# Arduino.net
KiCad netlist of a schematic drawn in Altium Designer
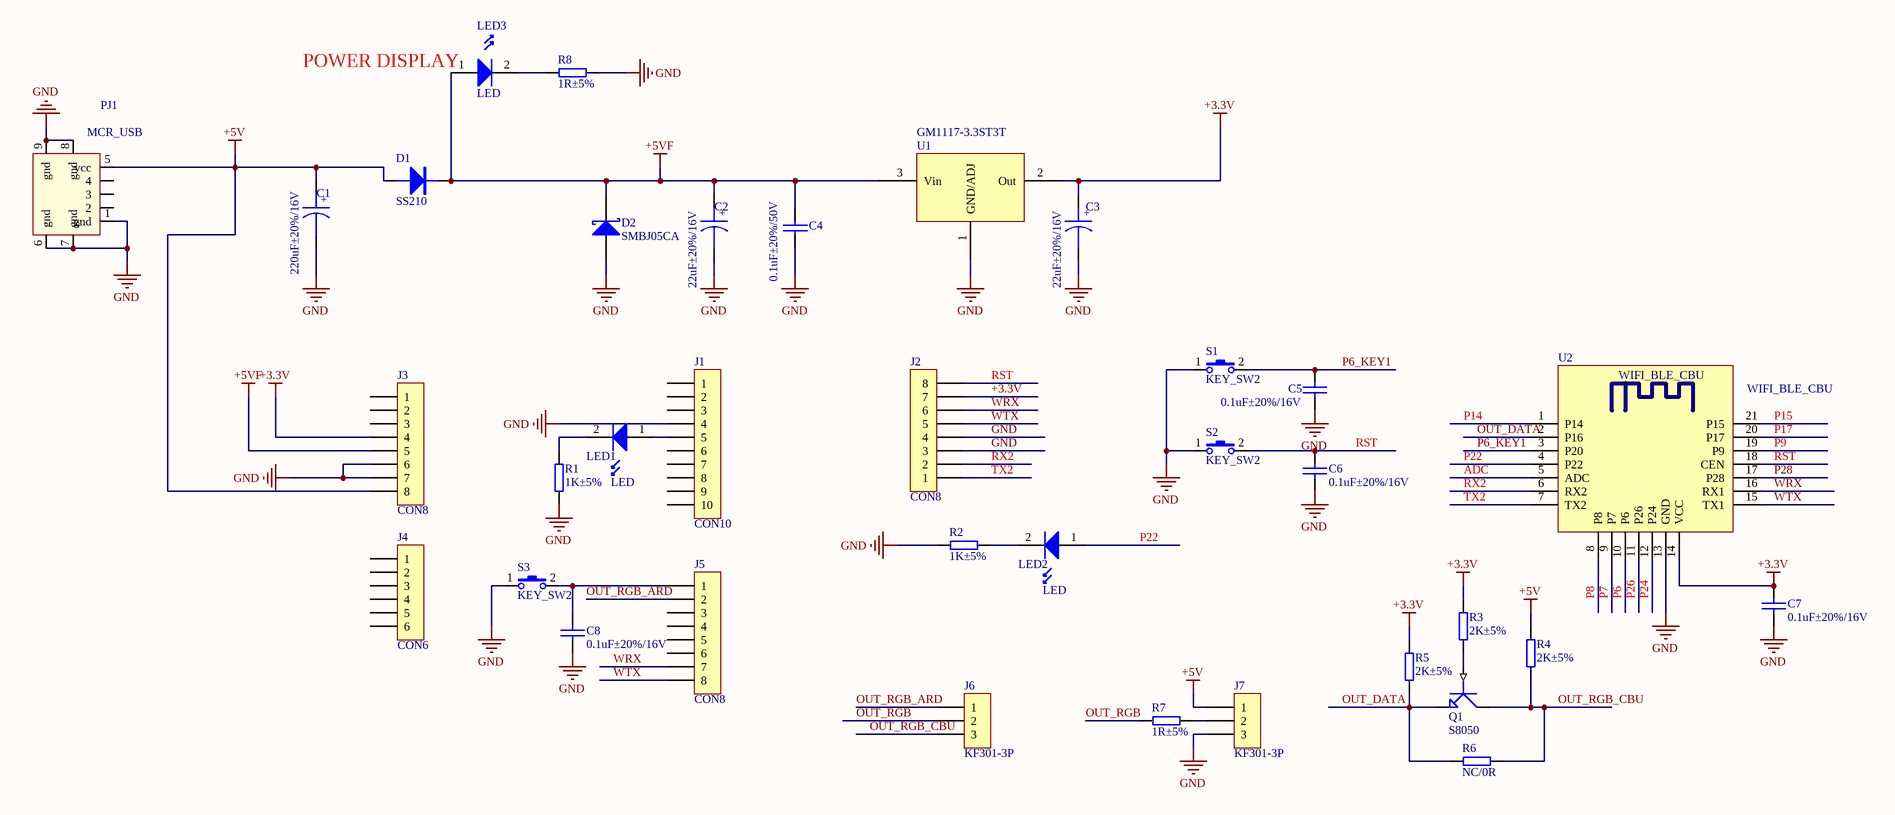
[diagram p0: Arduino幻彩灯带.SchDoc]

(export (version "E")
  (design (tool "Eeschema 10.0.6"))
  (components
    (comp (ref "C1")
      (value "220uF±20%/16V")
      (footprint "CD0.15")
      (description "Capacitor")
      (libsource (lib "*") (part "CAPACITOR POL"))
    )
    (comp (ref "C2")
      (value "22uF±20%/16V")
      (footprint "钽电容B3528")
      (description "Capacitor")
      (libsource (lib "*") (part "CAPACITOR POL"))
    )
    (comp (ref "C3")
      (value "22uF±20%/16V")
      (footprint "钽电容B3528")
      (description "Capacitor")
      (libsource (lib "*") (part "CAPACITOR POL"))
    )
    (comp (ref "C4")
      (value "0.1uF±20%/50V")
      (footprint "C0603")
      (description "Capacitor")
      (libsource (lib "昊华元件库sch") (part "CAP"))
    )
    (comp (ref "C5")
      (value "0.1uF±20%/16V")
      (footprint "C0603")
      (description "Capacitor")
      (libsource (lib "昊华元件库sch") (part "CAP"))
    )
    (comp (ref "C6")
      (value "0.1uF±20%/16V")
      (footprint "C0603")
      (description "Capacitor")
      (libsource (lib "昊华元件库sch") (part "CAP"))
    )
    (comp (ref "C7")
      (value "0.1uF±20%/16V")
      (footprint "C0603")
      (description "Capacitor")
      (libsource (lib "昊华元件库sch") (part "CAP"))
    )
    (comp (ref "C8")
      (value "0.1uF±20%/16V")
      (footprint "C0603")
      (description "Capacitor")
      (libsource (lib "昊华元件库sch") (part "CAP"))
    )
    (comp (ref "D1")
      (value "SS210")
      (footprint "SMA(DO-214AC)")
      (description "Diode")
      (libsource (lib "小马元件库sch") (part "Diode1"))
    )
    (comp (ref "D2")
      (value "SMBJ05CA")
      (footprint "SMB(DO-214AA)")
      (description "Schottky Diode")
      (fields (field (name "MFR") "Toshiba"))
      (libsource (lib "Miscellaneous Devices") (part "D Schottky"))
    )
    (comp (ref "J1")
      (value "CON10")
      (footprint "HDR1X10Z")
      (description "Connector")
      (libsource (lib "小马元件库sch") (part "CON10"))
    )
    (comp (ref "J2")
      (value "CON8")
      (footprint "HDR1X8Z")
      (description "Connector")
      (libsource (lib "") (part "CON8_1"))
    )
    (comp (ref "J3")
      (value "CON8")
      (footprint "HDR1X8Z")
      (description "Connector")
      (libsource (lib "小马元件库sch") (part "CON8"))
    )
    (comp (ref "J4")
      (value "CON6")
      (footprint "HDR1X6Z")
      (description "Connector")
      (libsource (lib "小马元件库sch") (part "CON6"))
    )
    (comp (ref "J5")
      (value "CON8")
      (footprint "HDR1X8Z")
      (description "Connector")
      (libsource (lib "小马元件库sch") (part "CON8"))
    )
    (comp (ref "J6")
      (value "KF301-3P")
      (footprint "SIP3 - 2.54")
      (description "Connector")
      (libsource (lib "小马元件库sch") (part "CON3"))
    )
    (comp (ref "J7")
      (value "KF301-3P")
      (footprint "SIP3 - 2.54")
      (description "Connector")
      (libsource (lib "小马元件库sch") (part "CON3"))
    )
    (comp (ref "LED1")
      (value "LED")
      (footprint "LED0805_1")
      (fields (field (name "PUBLISHER") "*"))
      (libsource (lib "小马元件库sch") (part "LED"))
    )
    (comp (ref "LED2")
      (value "LED")
      (footprint "LED0805_1")
      (fields (field (name "PUBLISHER") "*"))
      (libsource (lib "小马元件库sch") (part "LED"))
    )
    (comp (ref "LED3")
      (value "LED")
      (footprint "LED0805_1")
      (fields (field (name "PUBLISHER") "*"))
      (libsource (lib "小马元件库sch") (part "LED"))
    )
    (comp (ref "PJ1")
      (value "MCR_USB")
      (footprint "MICRO_USB-NEW-16.12.12")
      (fields (field (name "PUBLISHER") "*"))
      (libsource (lib "昊华元件库sch") (part "MCR_USB"))
    )
    (comp (ref "Q1")
      (value "S8050")
      (footprint "SOT-23-NPN")
      (description "NPN Transistor")
      (libsource (lib "小马元件库sch") (part "NPN"))
    )
    (comp (ref "R1") (value "1K±5%") (footprint "R0603") (libsource (lib "昊华元件库sch") (part "RES5")))
    (comp (ref "R2") (value "1K±5%") (footprint "R0603") (libsource (lib "昊华元件库sch") (part "RES5")))
    (comp (ref "R3") (value "2K±5%") (footprint "R0603") (libsource (lib "昊华元件库sch") (part "RES5")))
    (comp (ref "R4") (value "2K±5%") (footprint "R0603") (libsource (lib "昊华元件库sch") (part "RES5")))
    (comp (ref "R5") (value "2K±5%") (footprint "R0603") (libsource (lib "昊华元件库sch") (part "RES5")))
    (comp (ref "R6") (value "NC/0R") (footprint "R0603") (libsource (lib "昊华元件库sch") (part "RES5")))
    (comp (ref "R7") (value "1R±5%") (footprint "R0603") (libsource (lib "昊华元件库sch") (part "RES5")))
    (comp (ref "R8") (value "1R±5%") (footprint "R0603") (libsource (lib "昊华元件库sch") (part "RES5")))
    (comp (ref "S1") (value "KEY_SW2") (footprint "KEY4-SMD") (libsource (lib "小马元件库sch") (part "KEY_SW2")))
    (comp (ref "S2") (value "KEY_SW2") (footprint "KEY4-SMD") (libsource (lib "小马元件库sch") (part "KEY_SW2")))
    (comp (ref "S3") (value "KEY_SW2") (footprint "KEY4-SMD") (libsource (lib "小马元件库sch") (part "KEY_SW2")))
    (comp (ref "U1") (value "GM1117-3.3ST3T") (footprint "SOT-223") (libsource (lib "mylib") (part "GM1117")))
    (comp (ref "U2")
      (value "WIFI_BLE_CBU")
      (footprint "WIFI_BLE_CBU")
      (description "Module")
      (libsource (lib "TYModeSchlib V03") (part "WIFI_BLE_CBU"))
    )
  )
  (nets
    (net (code "1") (name "+3.3V") (class "Default")
      (node (ref "C3") (pin "1") (pinfunction "1_1") (pintype "passive"))
      (node (ref "C7") (pin "2") (pinfunction "2_2") (pintype "passive"))
      (node (ref "J2") (pin "7") (pinfunction "7_7") (pintype "passive"))
      (node (ref "J3") (pin "4") (pinfunction "4_4") (pintype "passive"))
      (node (ref "R3") (pin "1") (pinfunction "1_1") (pintype "passive"))
      (node (ref "R5") (pin "1") (pinfunction "1_1") (pintype "passive"))
      (node (ref "U1") (pin "2") (pinfunction "Out_2") (pintype "passive"))
      (node (ref "U2") (pin "14") (pinfunction "VCC_14") (pintype "passive"))
    )
    (net (code "2") (name "+5V") (class "Default")
      (node (ref "C1") (pin "1") (pinfunction "1_1") (pintype "passive"))
      (node (ref "D1") (pin "1") (pinfunction "1_1") (pintype "passive"))
      (node (ref "J3") (pin "8") (pinfunction "8_8") (pintype "passive"))
      (node (ref "J7") (pin "1") (pinfunction "1_1") (pintype "passive"))
      (node (ref "PJ1") (pin "5") (pinfunction "vcc_5") (pintype "passive"))
      (node (ref "R4") (pin "1") (pinfunction "1_1") (pintype "passive"))
    )
    (net (code "3") (name "+5VF") (class "Default")
      (node (ref "C2") (pin "1") (pinfunction "1_1") (pintype "passive"))
      (node (ref "C4") (pin "1") (pinfunction "1_1") (pintype "passive"))
      (node (ref "D1") (pin "2") (pinfunction "2_2") (pintype "passive"))
      (node (ref "D2") (pin "2") (pinfunction "K_2") (pintype "passive"))
      (node (ref "J3") (pin "5") (pinfunction "5_5") (pintype "passive"))
      (node (ref "LED3") (pin "1") (pinfunction "1_1") (pintype "passive"))
      (node (ref "U1") (pin "3") (pinfunction "Vin_3") (pintype "passive"))
    )
    (net (code "4") (name "/ADC") (class "Default")
      (node (ref "U2") (pin "5") (pinfunction "ADC_5") (pintype "passive"))
    )
    (net (code "5") (name "/OUT_DATA") (class "Default")
      (node (ref "Q1") (pin "1") (pinfunction "E_1") (pintype "passive"))
      (node (ref "R5") (pin "2") (pinfunction "2_2") (pintype "passive"))
      (node (ref "R6") (pin "1") (pinfunction "1_1") (pintype "passive"))
      (node (ref "U2") (pin "2") (pinfunction "P16_2") (pintype "passive"))
    )
    (net (code "6") (name "/OUT_RGB") (class "Default")
      (node (ref "J6") (pin "2") (pinfunction "2_2") (pintype "passive"))
      (node (ref "R7") (pin "1") (pinfunction "1_1") (pintype "passive"))
    )
    (net (code "7") (name "/OUT_RGB_ARD") (class "Default")
      (node (ref "J5") (pin "2") (pinfunction "2_2") (pintype "passive"))
      (node (ref "J6") (pin "1") (pinfunction "1_1") (pintype "passive"))
    )
    (net (code "8") (name "/OUT_RGB_CBU") (class "Default")
      (node (ref "J6") (pin "3") (pinfunction "3_3") (pintype "passive"))
      (node (ref "Q1") (pin "3") (pinfunction "C_3") (pintype "passive"))
      (node (ref "R4") (pin "2") (pinfunction "2_2") (pintype "passive"))
      (node (ref "R6") (pin "2") (pinfunction "2_2") (pintype "passive"))
    )
    (net (code "9") (name "/P6") (class "Default")
      (node (ref "U2") (pin "10") (pinfunction "P6_10") (pintype "passive"))
    )
    (net (code "10") (name "/P6_KEY1") (class "Default")
      (node (ref "C5") (pin "2") (pinfunction "2_2") (pintype "passive"))
      (node (ref "S1") (pin "2") (pinfunction "2_2") (pintype "passive"))
      (node (ref "U2") (pin "3") (pinfunction "P20_3") (pintype "passive"))
    )
    (net (code "11") (name "/P7") (class "Default")
      (node (ref "U2") (pin "9") (pinfunction "P7_9") (pintype "passive"))
    )
    (net (code "12") (name "/P8") (class "Default")
      (node (ref "U2") (pin "8") (pinfunction "P8_8") (pintype "passive"))
    )
    (net (code "13") (name "/P9") (class "Default")
      (node (ref "U2") (pin "19") (pinfunction "P9_19") (pintype "passive"))
    )
    (net (code "14") (name "/P14") (class "Default")
      (node (ref "U2") (pin "1") (pinfunction "P14_1") (pintype "passive"))
    )
    (net (code "15") (name "/P15") (class "Default")
      (node (ref "U2") (pin "21") (pinfunction "P15_21") (pintype "passive"))
    )
    (net (code "16") (name "/P17") (class "Default")
      (node (ref "U2") (pin "20") (pinfunction "P17_20") (pintype "passive"))
    )
    (net (code "17") (name "/P22") (class "Default")
      (node (ref "LED2") (pin "1") (pinfunction "1_1") (pintype "passive"))
      (node (ref "U2") (pin "4") (pinfunction "P22_4") (pintype "passive"))
    )
    (net (code "18") (name "/P24") (class "Default")
      (node (ref "U2") (pin "12") (pinfunction "P24_12") (pintype "passive"))
    )
    (net (code "19") (name "/P26") (class "Default")
      (node (ref "U2") (pin "11") (pinfunction "P26_11") (pintype "passive"))
    )
    (net (code "20") (name "/P28") (class "Default")
      (node (ref "U2") (pin "17") (pinfunction "P28_17") (pintype "passive"))
    )
    (net (code "21") (name "/RST") (class "Default")
      (node (ref "C6") (pin "1") (pinfunction "1_1") (pintype "passive"))
      (node (ref "J2") (pin "8") (pinfunction "8_8") (pintype "passive"))
      (node (ref "S2") (pin "2") (pinfunction "2_2") (pintype "passive"))
      (node (ref "U2") (pin "18") (pinfunction "CEN_18") (pintype "passive"))
    )
    (net (code "22") (name "/RX2") (class "Default")
      (node (ref "J2") (pin "2") (pinfunction "2_2") (pintype "passive"))
      (node (ref "U2") (pin "6") (pinfunction "RX2_6") (pintype "passive"))
    )
    (net (code "23") (name "/TX2") (class "Default")
      (node (ref "J2") (pin "1") (pinfunction "1_1") (pintype "passive"))
      (node (ref "U2") (pin "7") (pinfunction "TX2_7") (pintype "passive"))
    )
    (net (code "24") (name "/WRX") (class "Default")
      (node (ref "J2") (pin "6") (pinfunction "6_6") (pintype "passive"))
      (node (ref "J5") (pin "7") (pinfunction "7_7") (pintype "passive"))
      (node (ref "U2") (pin "16") (pinfunction "RX1_16") (pintype "passive"))
    )
    (net (code "25") (name "/WTX") (class "Default")
      (node (ref "J2") (pin "5") (pinfunction "5_5") (pintype "passive"))
      (node (ref "J5") (pin "8") (pinfunction "8_8") (pintype "passive"))
      (node (ref "U2") (pin "15") (pinfunction "TX1_15") (pintype "passive"))
    )
    (net (code "26") (name "GND") (class "Default")
      (node (ref "C1") (pin "2") (pinfunction "2_2") (pintype "passive"))
      (node (ref "C2") (pin "2") (pinfunction "2_2") (pintype "passive"))
      (node (ref "C3") (pin "2") (pinfunction "2_2") (pintype "passive"))
      (node (ref "C4") (pin "2") (pinfunction "2_2") (pintype "passive"))
      (node (ref "C5") (pin "1") (pinfunction "1_1") (pintype "passive"))
      (node (ref "C6") (pin "2") (pinfunction "2_2") (pintype "passive"))
      (node (ref "C7") (pin "1") (pinfunction "1_1") (pintype "passive"))
      (node (ref "C8") (pin "1") (pinfunction "1_1") (pintype "passive"))
      (node (ref "D2") (pin "1") (pinfunction "A_1") (pintype "passive"))
      (node (ref "J1") (pin "4") (pinfunction "4_4") (pintype "passive"))
      (node (ref "J2") (pin "3") (pinfunction "3_3") (pintype "passive"))
      (node (ref "J2") (pin "4") (pinfunction "4_4") (pintype "passive"))
      (node (ref "J3") (pin "6") (pinfunction "6_6") (pintype "passive"))
      (node (ref "J3") (pin "7") (pinfunction "7_7") (pintype "passive"))
      (node (ref "J7") (pin "3") (pinfunction "3_3") (pintype "passive"))
      (node (ref "PJ1") (pin "1") (pinfunction "gnd_1") (pintype "passive"))
      (node (ref "PJ1") (pin "6") (pinfunction "gnd_6") (pintype "passive"))
      (node (ref "PJ1") (pin "7") (pinfunction "gnd_7") (pintype "passive"))
      (node (ref "PJ1") (pin "8") (pinfunction "gnd_8") (pintype "passive"))
      (node (ref "PJ1") (pin "9") (pinfunction "gnd_9") (pintype "passive"))
      (node (ref "R1") (pin "1") (pinfunction "1_1") (pintype "passive"))
      (node (ref "R2") (pin "2") (pinfunction "2_2") (pintype "passive"))
      (node (ref "R8") (pin "2") (pinfunction "2_2") (pintype "passive"))
      (node (ref "S1") (pin "1") (pinfunction "1_1") (pintype "passive"))
      (node (ref "S2") (pin "1") (pinfunction "1_1") (pintype "passive"))
      (node (ref "S3") (pin "1") (pinfunction "1_1") (pintype "passive"))
      (node (ref "U1") (pin "1") (pinfunction "GND/ADJ_1") (pintype "passive"))
      (node (ref "U2") (pin "13") (pinfunction "GND_13") (pintype "passive"))
    )
    (net (code "27") (name "Net-(C8-Pad2)") (class "Default")
      (node (ref "C8") (pin "2") (pinfunction "2_2") (pintype "passive"))
      (node (ref "J5") (pin "1") (pinfunction "1_1") (pintype "passive"))
      (node (ref "S3") (pin "2") (pinfunction "2_2") (pintype "passive"))
    )
    (net (code "28") (name "Net-(J1-Pad5)") (class "Default")
      (node (ref "J1") (pin "5") (pinfunction "5_5") (pintype "passive"))
      (node (ref "LED1") (pin "1") (pinfunction "1_1") (pintype "passive"))
    )
    (net (code "29") (name "Net-(J7-Pad2)") (class "Default")
      (node (ref "J7") (pin "2") (pinfunction "2_2") (pintype "passive"))
      (node (ref "R7") (pin "2") (pinfunction "2_2") (pintype "passive"))
    )
    (net (code "30") (name "Net-(LED1-Pad2)") (class "Default")
      (node (ref "LED1") (pin "2") (pinfunction "2_2") (pintype "passive"))
      (node (ref "R1") (pin "2") (pinfunction "2_2") (pintype "passive"))
    )
    (net (code "31") (name "Net-(LED2-Pad2)") (class "Default")
      (node (ref "LED2") (pin "2") (pinfunction "2_2") (pintype "passive"))
      (node (ref "R2") (pin "1") (pinfunction "1_1") (pintype "passive"))
    )
    (net (code "32") (name "Net-(LED3-Pad2)") (class "Default")
      (node (ref "LED3") (pin "2") (pinfunction "2_2") (pintype "passive"))
      (node (ref "R8") (pin "1") (pinfunction "1_1") (pintype "passive"))
    )
    (net (code "33") (name "Net-(Q1-B)") (class "Default")
      (node (ref "Q1") (pin "2") (pinfunction "B_2") (pintype "input"))
      (node (ref "R3") (pin "2") (pinfunction "2_2") (pintype "passive"))
    )
    (net (code "34") (name "unconnected-(J1-Pad1)") (class "Default")
      (node (ref "J1") (pin "1") (pinfunction "1_1") (pintype "passive"))
    )
    (net (code "35") (name "unconnected-(J1-Pad2)") (class "Default")
      (node (ref "J1") (pin "2") (pinfunction "2_2") (pintype "passive"))
    )
    (net (code "36") (name "unconnected-(J1-Pad3)") (class "Default")
      (node (ref "J1") (pin "3") (pinfunction "3_3") (pintype "passive"))
    )
    (net (code "37") (name "unconnected-(J1-Pad6)") (class "Default")
      (node (ref "J1") (pin "6") (pinfunction "6_6") (pintype "passive"))
    )
    (net (code "38") (name "unconnected-(J1-Pad7)") (class "Default")
      (node (ref "J1") (pin "7") (pinfunction "7_7") (pintype "passive"))
    )
    (net (code "39") (name "unconnected-(J1-Pad8)") (class "Default")
      (node (ref "J1") (pin "8") (pinfunction "8_8") (pintype "passive"))
    )
    (net (code "40") (name "unconnected-(J1-Pad9)") (class "Default")
      (node (ref "J1") (pin "9") (pinfunction "9_9") (pintype "passive"))
    )
    (net (code "41") (name "unconnected-(J1-Pad10)") (class "Default")
      (node (ref "J1") (pin "10") (pinfunction "10_10") (pintype "passive"))
    )
    (net (code "42") (name "unconnected-(J3-Pad1)") (class "Default")
      (node (ref "J3") (pin "1") (pinfunction "1_1") (pintype "passive"))
    )
    (net (code "43") (name "unconnected-(J3-Pad2)") (class "Default")
      (node (ref "J3") (pin "2") (pinfunction "2_2") (pintype "passive"))
    )
    (net (code "44") (name "unconnected-(J3-Pad3)") (class "Default")
      (node (ref "J3") (pin "3") (pinfunction "3_3") (pintype "passive"))
    )
    (net (code "45") (name "unconnected-(J4-Pad1)") (class "Default")
      (node (ref "J4") (pin "1") (pinfunction "1_1") (pintype "passive"))
    )
    (net (code "46") (name "unconnected-(J4-Pad2)") (class "Default")
      (node (ref "J4") (pin "2") (pinfunction "2_2") (pintype "passive"))
    )
    (net (code "47") (name "unconnected-(J4-Pad3)") (class "Default")
      (node (ref "J4") (pin "3") (pinfunction "3_3") (pintype "passive"))
    )
    (net (code "48") (name "unconnected-(J4-Pad4)") (class "Default")
      (node (ref "J4") (pin "4") (pinfunction "4_4") (pintype "passive"))
    )
    (net (code "49") (name "unconnected-(J4-Pad5)") (class "Default")
      (node (ref "J4") (pin "5") (pinfunction "5_5") (pintype "passive"))
    )
    (net (code "50") (name "unconnected-(J4-Pad6)") (class "Default")
      (node (ref "J4") (pin "6") (pinfunction "6_6") (pintype "passive"))
    )
    (net (code "51") (name "unconnected-(J5-Pad3)") (class "Default")
      (node (ref "J5") (pin "3") (pinfunction "3_3") (pintype "passive"))
    )
    (net (code "52") (name "unconnected-(J5-Pad4)") (class "Default")
      (node (ref "J5") (pin "4") (pinfunction "4_4") (pintype "passive"))
    )
    (net (code "53") (name "unconnected-(J5-Pad5)") (class "Default")
      (node (ref "J5") (pin "5") (pinfunction "5_5") (pintype "passive"))
    )
    (net (code "54") (name "unconnected-(J5-Pad6)") (class "Default")
      (node (ref "J5") (pin "6") (pinfunction "6_6") (pintype "passive"))
    )
    (net (code "55") (name "unconnected-(PJ1-Pad2)") (class "Default")
      (node (ref "PJ1") (pin "2") (pinfunction "2_2") (pintype "passive"))
    )
    (net (code "56") (name "unconnected-(PJ1-Pad3)") (class "Default")
      (node (ref "PJ1") (pin "3") (pinfunction "3_3") (pintype "passive"))
    )
    (net (code "57") (name "unconnected-(PJ1-Pad4)") (class "Default")
      (node (ref "PJ1") (pin "4") (pinfunction "4_4") (pintype "passive"))
    )
  )
)
